# main.net
KiCad netlist of a schematic drawn in EAGLE
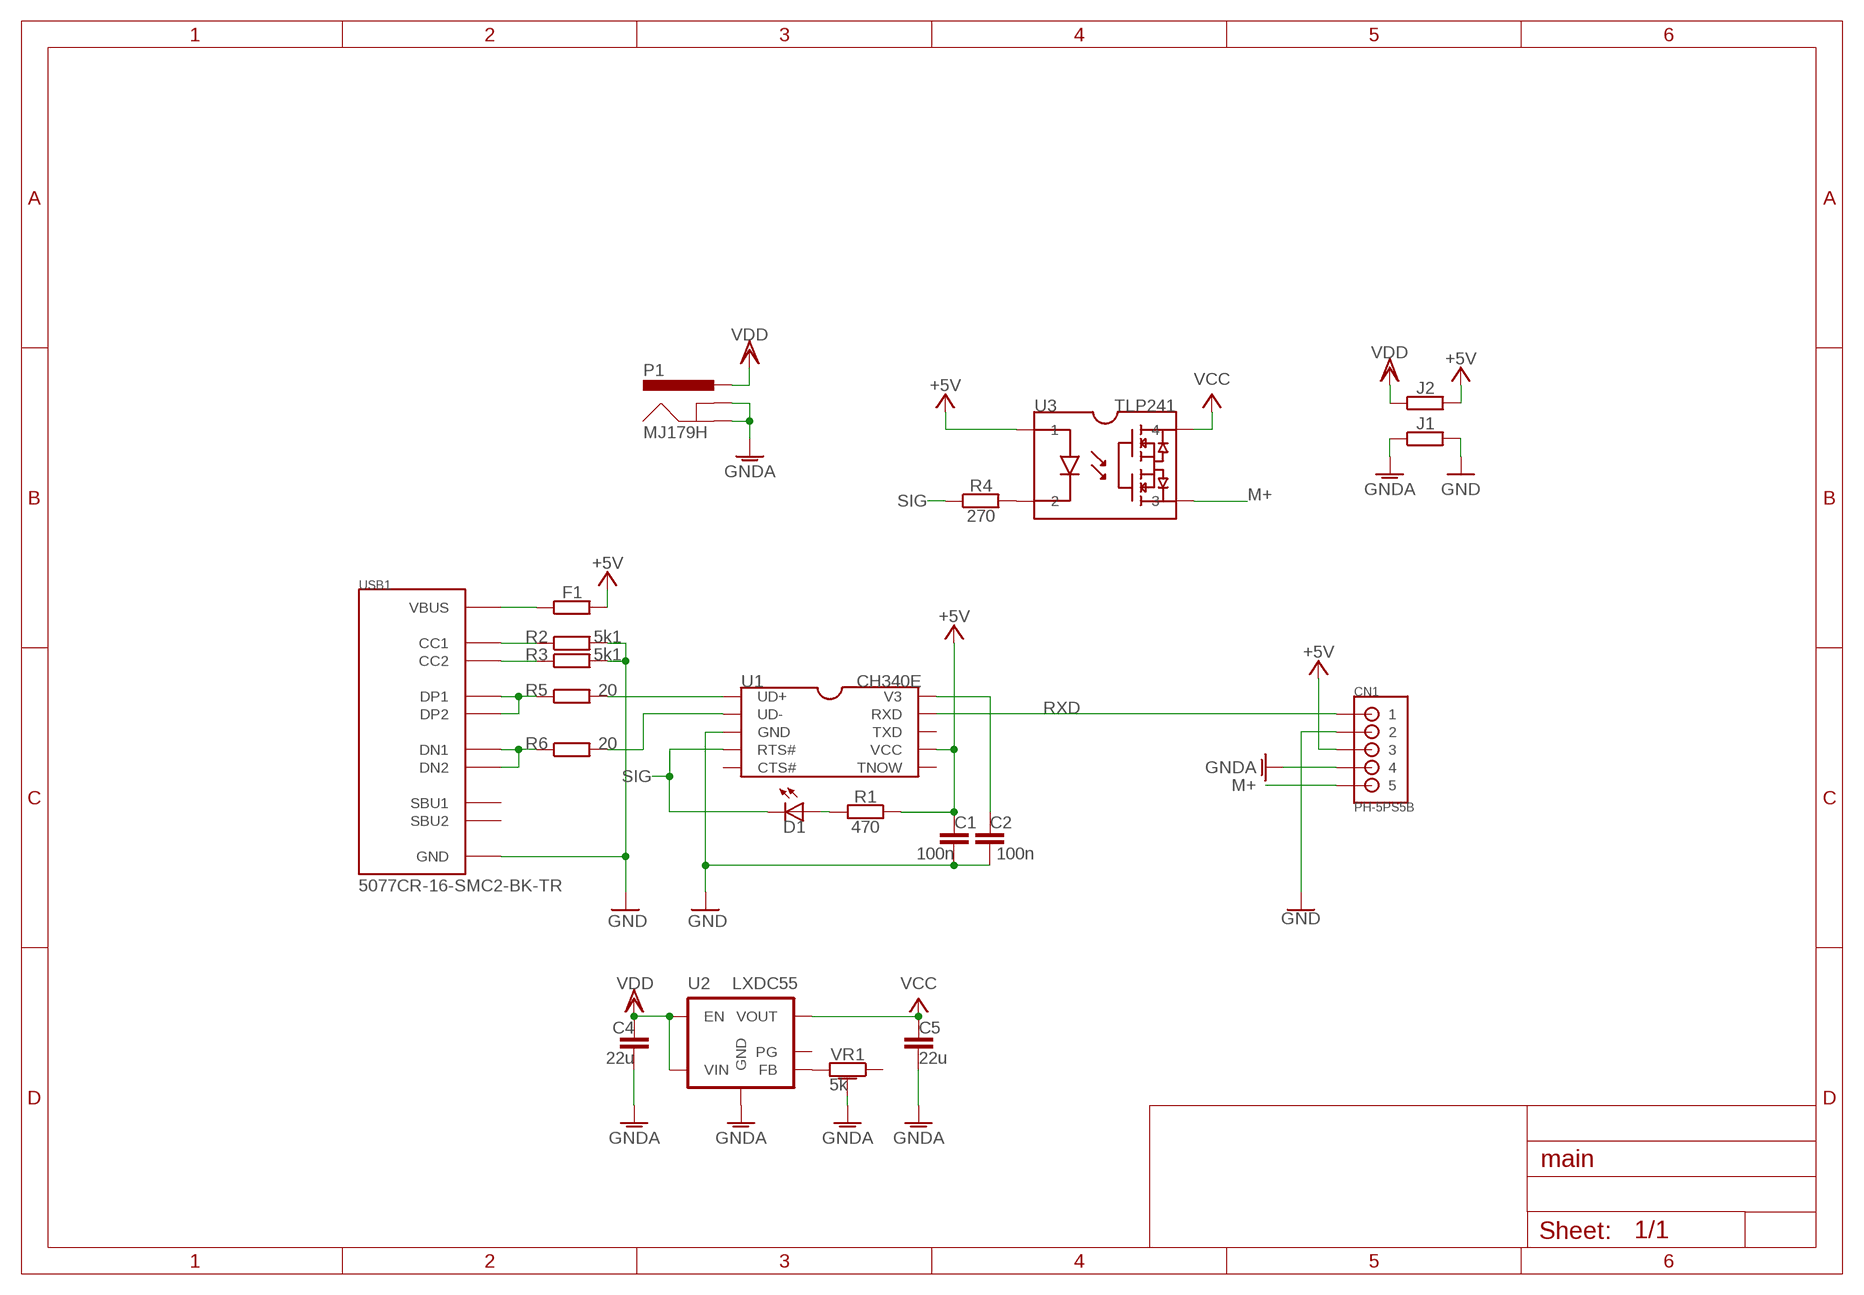
[diagram p0: schematic, sheet 1]

(export (version "E")
  (design (tool "Eeschema 10.0.6"))
  (components
    (comp (ref "C1")
      (value "100n")
      (footprint "eagle-import:C1608")
      (libsource (lib "eagle-import") (part "CAPACITOR1608"))
    )
    (comp (ref "C2")
      (value "100n")
      (footprint "eagle-import:C1608")
      (libsource (lib "eagle-import") (part "CAPACITOR1608"))
    )
    (comp (ref "C4")
      (value "22u")
      (footprint "eagle-import:C1608")
      (libsource (lib "eagle-import") (part "CAPACITOR1608"))
    )
    (comp (ref "C5")
      (value "22u")
      (footprint "eagle-import:C1608")
      (libsource (lib "eagle-import") (part "CAPACITOR1608"))
    )
    (comp (ref "CN1")
      (value "PH-5PS5B")
      (footprint "eagle-import:S5B-PH-K-S")
      (fields (field (name "MPN") "S5B-PH-K-S"))
      (libsource (lib "eagle-import") (part "PH-5PS5B"))
    )
    (comp (ref "D1")
      (value "LED1608B")
      (footprint "eagle-import:LED1608B")
      (libsource (lib "eagle-import") (part "LED1608B"))
    )
    (comp (ref "F1")
      (value "5k1")
      (footprint "eagle-import:R3225")
      (libsource (lib "eagle-import") (part "RESISTER3225"))
    )
    (comp (ref "J1")
      (value "JUMPER2012")
      (footprint "eagle-import:J2012")
      (libsource (lib "eagle-import") (part "JUMPER2012"))
    )
    (comp (ref "J2")
      (value "JUMPER2012")
      (footprint "eagle-import:J2012")
      (libsource (lib "eagle-import") (part "JUMPER2012"))
    )
    (comp (ref "P1")
      (value "DC-JACKMJ179PH")
      (footprint "eagle-import:MJ179PH")
      (fields (field (name "PART#") "MJ179H"))
      (libsource (lib "eagle-import") (part "DC-JACKMJ179PH"))
    )
    (comp (ref "R1")
      (value "470")
      (footprint "eagle-import:R1608")
      (libsource (lib "eagle-import") (part "RESISTER1608"))
    )
    (comp (ref "R2")
      (value "5k1")
      (footprint "eagle-import:R1608")
      (libsource (lib "eagle-import") (part "RESISTER1608"))
    )
    (comp (ref "R3")
      (value "5k1")
      (footprint "eagle-import:R1608")
      (libsource (lib "eagle-import") (part "RESISTER1608"))
    )
    (comp (ref "R4")
      (value "270")
      (footprint "eagle-import:R1608")
      (libsource (lib "eagle-import") (part "RESISTER1608"))
    )
    (comp (ref "R5")
      (value "20")
      (footprint "eagle-import:R1608")
      (libsource (lib "eagle-import") (part "RESISTER1608"))
    )
    (comp (ref "R6")
      (value "20")
      (footprint "eagle-import:R1608")
      (libsource (lib "eagle-import") (part "RESISTER1608"))
    )
    (comp (ref "U1")
      (value "CH340EMSOP")
      (footprint "eagle-import:MSOP-05-10P")
      (fields (field (name "PART#") "CH340E"))
      (libsource (lib "eagle-import") (part "CH340EMSOP"))
    )
    (comp (ref "U2")
      (value "LXDC55FAAA-203SMD-GND")
      (footprint "eagle-import:LXDC55FAAA-203-GND")
      (fields (field (name "PART#") "LXDC55"))
      (libsource (lib "eagle-import") (part "LXDC55FAAA-203SMD-GND"))
    )
    (comp (ref "U3")
      (value "TLP241ADIP")
      (footprint "eagle-import:DIP-4P")
      (fields (field (name "PART#") "TLP241"))
      (libsource (lib "eagle-import") (part "TLP241ADIP"))
    )
    (comp (ref "USB1")
      (value "USB1")
      (footprint "eagle-import:5077CR-16-SMC2-BK-TR")
      (fields (field (name "PART#") "5077CR-16-SMC2-BK-TR"))
      (libsource (lib "eagle-import") (part "USB-CSMD"))
    )
    (comp (ref "VR1")
      (value "5k")
      (footprint "eagle-import:SEMIVR_3296W")
      (fields (field (name "RESISTER") "5k"))
      (libsource (lib "eagle-import") (part "SEMI_VR3296W"))
    )
  )
  (nets
    (net (code "1") (name "+5V") (class "Default")
      (node (ref "C1") (pin "P$1") (pinfunction "1_P$1") (pintype "passive"))
      (node (ref "CN1") (pin "3") (pinfunction "3_3") (pintype "bidirectional"))
      (node (ref "F1") (pin "P$2") (pinfunction "2_P$2") (pintype "passive"))
      (node (ref "J2") (pin "P$2") (pinfunction "2_P$2") (pintype "passive"))
      (node (ref "R1") (pin "P$1") (pinfunction "1_P$1") (pintype "passive"))
      (node (ref "U1") (pin "P$7") (pinfunction "VCC_P$7") (pintype "passive"))
      (node (ref "U3") (pin "P$1") (pinfunction "1_P$1") (pintype "passive"))
    )
    (net (code "2") (name "/M+") (class "Default")
      (node (ref "CN1") (pin "5") (pinfunction "5_5") (pintype "bidirectional"))
      (node (ref "U3") (pin "P$3") (pinfunction "3_P$3") (pintype "passive"))
    )
    (net (code "3") (name "/RXD") (class "Default")
      (node (ref "CN1") (pin "1") (pinfunction "1_1") (pintype "bidirectional"))
      (node (ref "U1") (pin "P$9") (pinfunction "RXD_P$9") (pintype "passive"))
    )
    (net (code "4") (name "/SIG") (class "Default")
      (node (ref "D1") (pin "P$2") (pinfunction "K_P$2") (pintype "passive"))
      (node (ref "R4") (pin "P$1") (pinfunction "1_P$1") (pintype "passive"))
      (node (ref "U1") (pin "P$4") (pinfunction "RTS#_P$4") (pintype "passive"))
    )
    (net (code "5") (name "GND") (class "Default")
      (node (ref "C1") (pin "P$2") (pinfunction "2_P$2") (pintype "passive"))
      (node (ref "C2") (pin "P$2") (pinfunction "2_P$2") (pintype "passive"))
      (node (ref "CN1") (pin "2") (pinfunction "2_2") (pintype "bidirectional"))
      (node (ref "J1") (pin "P$2") (pinfunction "2_P$2") (pintype "passive"))
      (node (ref "R2") (pin "P$2") (pinfunction "2_P$2") (pintype "passive"))
      (node (ref "R3") (pin "P$2") (pinfunction "2_P$2") (pintype "passive"))
      (node (ref "U1") (pin "P$3") (pinfunction "GND_P$3") (pintype "passive"))
      (node (ref "USB1") (pin "A1_B12") (pinfunction "GND_A1_B12") (pintype "bidirectional"))
      (node (ref "USB1") (pin "B1_A12") (pinfunction "GND_B1_A12") (pintype "bidirectional"))
      (node (ref "USB1") (pin "P$13") (pinfunction "GND_P$13") (pintype "bidirectional"))
      (node (ref "USB1") (pin "P$14") (pinfunction "GND_P$14") (pintype "bidirectional"))
      (node (ref "USB1") (pin "P$15") (pinfunction "GND_P$15") (pintype "bidirectional"))
      (node (ref "USB1") (pin "P$16") (pinfunction "GND_P$16") (pintype "bidirectional"))
      (node (ref "USB1") (pin "P$17") (pinfunction "GND_P$17") (pintype "bidirectional"))
      (node (ref "USB1") (pin "P$18") (pinfunction "GND_P$18") (pintype "bidirectional"))
      (node (ref "USB1") (pin "P$19") (pinfunction "GND_P$19") (pintype "bidirectional"))
      (node (ref "USB1") (pin "P$20") (pinfunction "GND_P$20") (pintype "bidirectional"))
    )
    (net (code "6") (name "GNDA") (class "Default")
      (node (ref "C4") (pin "P$2") (pinfunction "2_P$2") (pintype "passive"))
      (node (ref "C5") (pin "P$2") (pinfunction "2_P$2") (pintype "passive"))
      (node (ref "CN1") (pin "4") (pinfunction "4_4") (pintype "bidirectional"))
      (node (ref "J1") (pin "P$1") (pinfunction "1_P$1") (pintype "passive"))
      (node (ref "P1") (pin "BREAK") (pinfunction "GNDBREAK_BREAK") (pintype "bidirectional"))
      (node (ref "P1") (pin "BREAK1") (pinfunction "GNDBREAK_BREAK1") (pintype "bidirectional"))
      (node (ref "P1") (pin "GND") (pinfunction "GND_GND") (pintype "bidirectional"))
      (node (ref "P1") (pin "GND1") (pinfunction "GND_GND1") (pintype "bidirectional"))
      (node (ref "U2") (pin "P$15") (pinfunction "GND_P$15") (pintype "input"))
      (node (ref "VR1") (pin "P$3") (pinfunction "3_P$3") (pintype "passive"))
    )
    (net (code "7") (name "Net-(C2-1)") (class "Default")
      (node (ref "C2") (pin "P$1") (pinfunction "1_P$1") (pintype "passive"))
      (node (ref "U1") (pin "P$10") (pinfunction "V3_P$10") (pintype "passive"))
    )
    (net (code "8") (name "Net-(D1-A)") (class "Default")
      (node (ref "D1") (pin "P$1") (pinfunction "A_P$1") (pintype "passive"))
      (node (ref "R1") (pin "P$2") (pinfunction "2_P$2") (pintype "passive"))
    )
    (net (code "9") (name "Net-(F1-1)") (class "Default")
      (node (ref "F1") (pin "P$1") (pinfunction "1_P$1") (pintype "passive"))
      (node (ref "USB1") (pin "A4_B9") (pinfunction "VBUS_A4_B9") (pintype "bidirectional"))
      (node (ref "USB1") (pin "B4_A9") (pinfunction "VBUS_B4_A9") (pintype "bidirectional"))
    )
    (net (code "10") (name "Net-(R2-1)") (class "Default")
      (node (ref "R2") (pin "P$1") (pinfunction "1_P$1") (pintype "passive"))
      (node (ref "USB1") (pin "A5") (pinfunction "CC1_A5") (pintype "bidirectional"))
    )
    (net (code "11") (name "Net-(R3-1)") (class "Default")
      (node (ref "R3") (pin "P$1") (pinfunction "1_P$1") (pintype "passive"))
      (node (ref "USB1") (pin "B5") (pinfunction "CC2_B5") (pintype "bidirectional"))
    )
    (net (code "12") (name "Net-(R4-2)") (class "Default")
      (node (ref "R4") (pin "P$2") (pinfunction "2_P$2") (pintype "passive"))
      (node (ref "U3") (pin "P$2") (pinfunction "2_P$2") (pintype "passive"))
    )
    (net (code "13") (name "Net-(R5-1)") (class "Default")
      (node (ref "R5") (pin "P$1") (pinfunction "1_P$1") (pintype "passive"))
      (node (ref "USB1") (pin "A6") (pinfunction "DP1_A6") (pintype "bidirectional"))
      (node (ref "USB1") (pin "B6") (pinfunction "DP2_B6") (pintype "bidirectional"))
    )
    (net (code "14") (name "Net-(R5-2)") (class "Default")
      (node (ref "R5") (pin "P$2") (pinfunction "2_P$2") (pintype "passive"))
      (node (ref "U1") (pin "P$1") (pinfunction "UD+_P$1") (pintype "passive"))
    )
    (net (code "15") (name "Net-(R6-1)") (class "Default")
      (node (ref "R6") (pin "P$1") (pinfunction "1_P$1") (pintype "passive"))
      (node (ref "USB1") (pin "A7") (pinfunction "DN1_A7") (pintype "bidirectional"))
      (node (ref "USB1") (pin "B7") (pinfunction "DN2_B7") (pintype "bidirectional"))
    )
    (net (code "16") (name "Net-(R6-2)") (class "Default")
      (node (ref "R6") (pin "P$2") (pinfunction "2_P$2") (pintype "passive"))
      (node (ref "U1") (pin "P$2") (pinfunction "UD-_P$2") (pintype "passive"))
    )
    (net (code "17") (name "Net-(U2-FB)") (class "Default")
      (node (ref "U2") (pin "P$11") (pinfunction "FB_P$11") (pintype "passive"))
      (node (ref "VR1") (pin "P$2") (pinfunction "2_P$2") (pintype "passive"))
    )
    (net (code "18") (name "VCC") (class "Default")
      (node (ref "C5") (pin "P$1") (pinfunction "1_P$1") (pintype "passive"))
      (node (ref "U2") (pin "P$7") (pinfunction "VOUT_P$7") (pintype "passive"))
      (node (ref "U2") (pin "P$8") (pinfunction "VOUT_P$8") (pintype "passive"))
      (node (ref "U2") (pin "P$9") (pinfunction "VOUT_P$9") (pintype "passive"))
      (node (ref "U3") (pin "P$4") (pinfunction "4_P$4") (pintype "passive"))
    )
    (net (code "19") (name "VDD") (class "Default")
      (node (ref "C4") (pin "P$1") (pinfunction "1_P$1") (pintype "passive"))
      (node (ref "J2") (pin "P$1") (pinfunction "1_P$1") (pintype "passive"))
      (node (ref "P1") (pin "VCC") (pinfunction "PWR_VCC") (pintype "bidirectional"))
      (node (ref "P1") (pin "VCC1") (pinfunction "PWR_VCC1") (pintype "bidirectional"))
      (node (ref "U2") (pin "P$1") (pinfunction "EN_P$1") (pintype "input"))
      (node (ref "U2") (pin "P$3") (pinfunction "VIN_P$3") (pintype "input"))
      (node (ref "U2") (pin "P$4") (pinfunction "VIN_P$4") (pintype "input"))
      (node (ref "U2") (pin "P$5") (pinfunction "VIN_P$5") (pintype "input"))
    )
    (net (code "20") (name "unconnected-(U1-CTS#-PadP$5)") (class "Default")
      (node (ref "U1") (pin "P$5") (pinfunction "CTS#_P$5") (pintype "passive"))
    )
    (net (code "21") (name "unconnected-(U1-TNOW-PadP$6)") (class "Default")
      (node (ref "U1") (pin "P$6") (pinfunction "TNOW_P$6") (pintype "passive"))
    )
    (net (code "22") (name "unconnected-(U1-TXD-PadP$8)") (class "Default")
      (node (ref "U1") (pin "P$8") (pinfunction "TXD_P$8") (pintype "passive"))
    )
    (net (code "23") (name "unconnected-(U2-PG-PadP$10)") (class "Default")
      (node (ref "U2") (pin "P$10") (pinfunction "PG_P$10") (pintype "passive"))
    )
    (net (code "24") (name "unconnected-(USB1-SBU1-PadA8)") (class "Default")
      (node (ref "USB1") (pin "A8") (pinfunction "SBU1_A8") (pintype "bidirectional"))
    )
    (net (code "25") (name "unconnected-(USB1-SBU2-PadB8)") (class "Default")
      (node (ref "USB1") (pin "B8") (pinfunction "SBU2_B8") (pintype "bidirectional"))
    )
    (net (code "26") (name "unconnected-(VR1-1-PadP$1)") (class "Default")
      (node (ref "VR1") (pin "P$1") (pinfunction "1_P$1") (pintype "passive"))
    )
  )
)
